# Power_Supply.net
KiCad netlist of a schematic drawn in Altium Designer
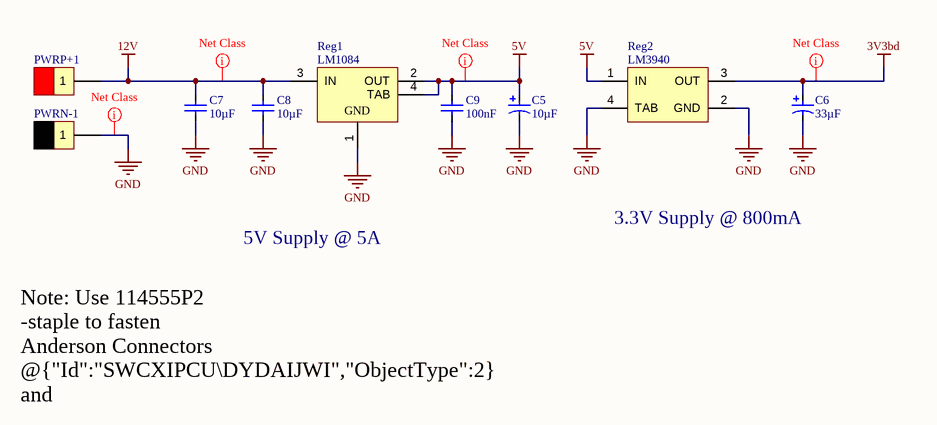
[diagram p0: Power Supply.SchDoc]

(export (version "E")
  (design (tool "Eeschema 10.0.6"))
  (components
    (comp (ref "C5")
      (value "10µF")
      (footprint "AVX-TPSB106K020R1000_L")
      (fields (field (name "Comment") "TPSB106K020R1000"))
      (libsource (lib "Advanced] Training Course - A365") (part "CAP_Polar Generic"))
    )
    (comp (ref "C6")
      (value "33µF")
      (footprint "FP-TAJY-MFG")
      (fields (field (name "Comment") "TAJY336K020RNJ"))
      (libsource (lib "Advanced] Training Course - A365") (part "CAP_Polar Generic"))
    )
    (comp (ref "C7")
      (value "10µF")
      (footprint "CAPC2013X135X45ML10T25")
      (fields (field (name "TOLERANCE") "10%") (field (name "Comment") "CAP_Murata"))
      (libsource (lib "Advanced] Training Course - A365") (part "CAP_Murata"))
    )
    (comp (ref "C8")
      (value "10µF")
      (footprint "CAPC2013X135X45ML10T25")
      (fields (field (name "TOLERANCE") "10%") (field (name "Comment") "CAP_Murata"))
      (libsource (lib "Advanced] Training Course - A365") (part "CAP_Murata"))
    )
    (comp (ref "C9")
      (value "100nF")
      (footprint "0603C_L")
      (fields (field (name "Comment") "Cap100nF_50V_0603"))
      (libsource (lib "Advanced] Training Course - A365") (part "CAP General"))
    )
    (comp (ref "PWRN-1")
      (value "Anderson-1Pin BLK_PCB_RHT")
      (footprint "Anderson_BLK_RHT_BOT")
      (description "Connector Accessory, Contact, Copper Alloy")
      (libsource (lib "Advanced] Training Course - A365") (part "Anderson-1Pin BLK_PCB_RHT"))
    )
    (comp (ref "PWRP+1")
      (value "Anderson-1Pin RED_PCB_RHT")
      (footprint "Anderson_RED_RHT_BOT")
      (description "Connector Accessory, Contact, Copper Alloy")
      (libsource (lib "TC - Altium Essentials Course A365 13") (part "Anderson-1Pin RED_PCB_RHT"))
    )
    (comp (ref "Reg1")
      (value "LM1084")
      (footprint "KTT0003B_L")
      (description "5A Low Dropout Positive Regulators, 3-pin TO-263, Pb-Free")
      (fields
        (field (name "MANUFACTURER") "Texas Instruments")
        (field (name "PARTNUMBER") "LM1084IS-5.0/NOPB")
        (field (name "AVAILABLE PREVIEW IMAGES") "2D")
      )
      (libsource (lib "Advanced] Training Course - A365") (part "LM1084"))
    )
    (comp (ref "Reg2")
      (value "LM3940")
      (footprint "SOT223")
      (description "1A Low Dropout Regulator for 5V to 3.3V Conversion, 4-pin SOT-223, Pb-Free")
      (fields
        (field (name "MANUFACTURER") "Texas Instruments")
        (field (name "MANUFACTURER PART NUMBER") "LM3940IMP-3.3/NOPB")
      )
      (libsource (lib "Advanced] Training Course - A365") (part "LM3940"))
    )
  )
  (nets
    (net (code "1") (name "3V3bd") (class "Default")
      (node (ref "C6") (pin "2") (pinfunction "2_2") (pintype "passive"))
      (node (ref "Reg2") (pin "3") (pinfunction "OUT_3") (pintype "power_in"))
    )
    (net (code "2") (name "5V") (class "Default")
      (node (ref "C5") (pin "2") (pinfunction "2_2") (pintype "passive"))
      (node (ref "C9") (pin "2") (pinfunction "2_2") (pintype "passive"))
      (node (ref "Reg1") (pin "2") (pinfunction "OUT_2") (pintype "power_in"))
      (node (ref "Reg1") (pin "4") (pinfunction "TAB_4") (pintype "power_in"))
      (node (ref "Reg2") (pin "1") (pinfunction "IN_1") (pintype "power_in"))
    )
    (net (code "3") (name "12V") (class "Default")
      (node (ref "C7") (pin "2") (pinfunction "2_2") (pintype "passive"))
      (node (ref "C8") (pin "2") (pinfunction "2_2") (pintype "passive"))
      (node (ref "PWRP+1") (pin "1") (pinfunction "1_1") (pintype "passive"))
      (node (ref "Reg1") (pin "3") (pinfunction "IN_3") (pintype "power_in"))
    )
    (net (code "4") (name "GND") (class "Default")
      (node (ref "C5") (pin "1") (pinfunction "1_1") (pintype "passive"))
      (node (ref "C6") (pin "1") (pinfunction "1_1") (pintype "passive"))
      (node (ref "C7") (pin "1") (pinfunction "1_1") (pintype "passive"))
      (node (ref "C8") (pin "1") (pinfunction "1_1") (pintype "passive"))
      (node (ref "C9") (pin "1") (pinfunction "1_1") (pintype "passive"))
      (node (ref "PWRN-1") (pin "1") (pinfunction "1_1") (pintype "passive"))
      (node (ref "Reg1") (pin "1") (pinfunction "GND_1") (pintype "power_in"))
      (node (ref "Reg2") (pin "2") (pinfunction "GND_2") (pintype "power_in"))
      (node (ref "Reg2") (pin "4") (pinfunction "TAB_4") (pintype "power_in"))
    )
  )
)
